# umodular_midi4_rev02.net
KiCad netlist of a schematic drawn in EAGLE
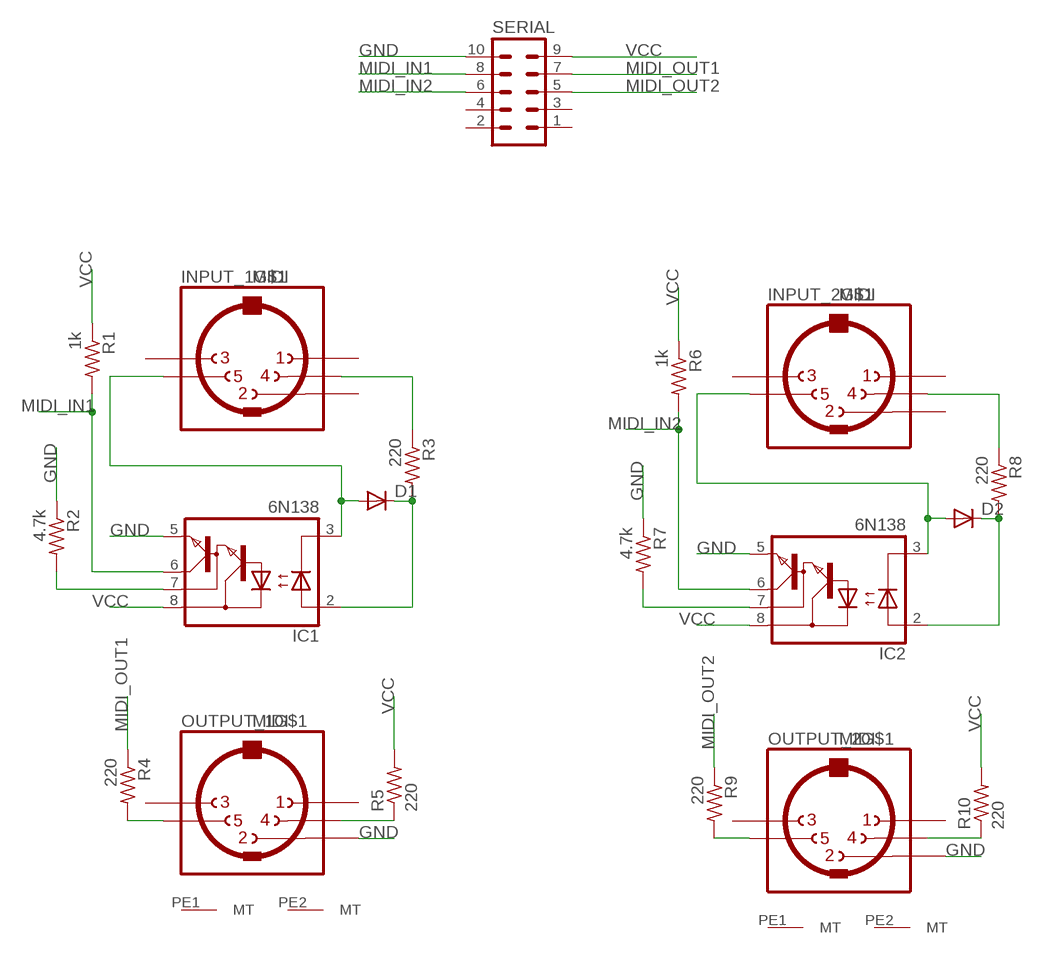
[diagram p0: schematic, sheet 1]

(export (version "E")
  (design (tool "Eeschema 10.0.6"))
  (components
    (comp (ref "D1")
      (value "1N4148DO35-7")
      (footprint "eagle-import:DO35-7")
      (libsource (lib "eagle-import") (part "1N4148DO35-7"))
    )
    (comp (ref "D2")
      (value "1N4148DO35-7")
      (footprint "eagle-import:DO35-7")
      (libsource (lib "eagle-import") (part "1N4148DO35-7"))
    )
    (comp (ref "IC1")
      (value "6N138")
      (footprint "eagle-import:DIL08")
      (fields (field (name "MF") "VISHAY/TELEFUNKEN"))
      (libsource (lib "eagle-import") (part "6N138"))
    )
    (comp (ref "IC2")
      (value "6N138")
      (footprint "eagle-import:DIL08")
      (fields (field (name "MF") "VISHAY/TELEFUNKEN"))
      (libsource (lib "eagle-import") (part "6N138"))
    )
    (comp (ref "INPUT_1")
      (value "MIDI")
      (footprint "eagle-import:CP-2350")
      (libsource (lib "eagle-import") (part "MIDIJACK"))
    )
    (comp (ref "INPUT_2")
      (value "MIDI")
      (footprint "eagle-import:CP-2350")
      (libsource (lib "eagle-import") (part "MIDIJACK"))
    )
    (comp (ref "OUTPUT_1")
      (value "MIDI")
      (footprint "eagle-import:CP-2350")
      (libsource (lib "eagle-import") (part "MIDIJACK"))
    )
    (comp (ref "OUTPUT_2")
      (value "MIDI")
      (footprint "eagle-import:CP-2350")
      (libsource (lib "eagle-import") (part "MIDIJACK"))
    )
    (comp (ref "R1")
      (value "1k")
      (footprint "eagle-import:0204_7@1")
      (libsource (lib "eagle-import") (part "R-US_0204/7"))
    )
    (comp (ref "R2")
      (value "4.7k")
      (footprint "eagle-import:0204_7@1")
      (libsource (lib "eagle-import") (part "R-US_0204/7"))
    )
    (comp (ref "R3")
      (value "220")
      (footprint "eagle-import:0204_7@1")
      (libsource (lib "eagle-import") (part "R-US_0204/7"))
    )
    (comp (ref "R4")
      (value "220")
      (footprint "eagle-import:0204_7@1")
      (libsource (lib "eagle-import") (part "R-US_0204/7"))
    )
    (comp (ref "R5")
      (value "220")
      (footprint "eagle-import:0204_7@1")
      (libsource (lib "eagle-import") (part "R-US_0204/7"))
    )
    (comp (ref "R6")
      (value "1k")
      (footprint "eagle-import:0204_7@1")
      (libsource (lib "eagle-import") (part "R-US_0204/7"))
    )
    (comp (ref "R7")
      (value "4.7k")
      (footprint "eagle-import:0204_7@1")
      (libsource (lib "eagle-import") (part "R-US_0204/7"))
    )
    (comp (ref "R8")
      (value "220")
      (footprint "eagle-import:0204_7@1")
      (libsource (lib "eagle-import") (part "R-US_0204/7"))
    )
    (comp (ref "R9")
      (value "220")
      (footprint "eagle-import:0204_7@1")
      (libsource (lib "eagle-import") (part "R-US_0204/7"))
    )
    (comp (ref "R10")
      (value "220")
      (footprint "eagle-import:0204_7@1")
      (libsource (lib "eagle-import") (part "R-US_0204/7"))
    )
    (comp (ref "SERIAL")
      (value "MA05-2")
      (footprint "eagle-import:MA05-2")
      (libsource (lib "eagle-import") (part "MA05-2"))
    )
  )
  (nets
    (net (code "1") (name "/GND") (class "Default")
      (node (ref "IC1") (pin "5") (pinfunction "GND_5") (pintype "passive"))
      (node (ref "IC2") (pin "5") (pinfunction "GND_5") (pintype "passive"))
      (node (ref "OUTPUT_1") (pin "2") (pinfunction "2_2") (pintype "passive"))
      (node (ref "OUTPUT_2") (pin "2") (pinfunction "2_2") (pintype "passive"))
      (node (ref "R2") (pin "1") (pinfunction "1_1") (pintype "passive"))
      (node (ref "R7") (pin "1") (pinfunction "1_1") (pintype "passive"))
      (node (ref "SERIAL") (pin "10") (pinfunction "10_10") (pintype "passive"))
    )
    (net (code "2") (name "/MIDI_IN1") (class "Default")
      (node (ref "IC1") (pin "6") (pinfunction "VO_6") (pintype "passive"))
      (node (ref "R1") (pin "2") (pinfunction "2_2") (pintype "passive"))
      (node (ref "SERIAL") (pin "8") (pinfunction "8_8") (pintype "passive"))
    )
    (net (code "3") (name "/MIDI_IN2") (class "Default")
      (node (ref "IC2") (pin "6") (pinfunction "VO_6") (pintype "passive"))
      (node (ref "R6") (pin "2") (pinfunction "2_2") (pintype "passive"))
      (node (ref "SERIAL") (pin "6") (pinfunction "6_6") (pintype "passive"))
    )
    (net (code "4") (name "/MIDI_OUT1") (class "Default")
      (node (ref "R4") (pin "1") (pinfunction "1_1") (pintype "passive"))
      (node (ref "SERIAL") (pin "7") (pinfunction "7_7") (pintype "passive"))
    )
    (net (code "5") (name "/MIDI_OUT2") (class "Default")
      (node (ref "R9") (pin "1") (pinfunction "1_1") (pintype "passive"))
      (node (ref "SERIAL") (pin "5") (pinfunction "5_5") (pintype "passive"))
    )
    (net (code "6") (name "/VCC") (class "Default")
      (node (ref "IC1") (pin "8") (pinfunction "VCC_8") (pintype "passive"))
      (node (ref "IC2") (pin "8") (pinfunction "VCC_8") (pintype "passive"))
      (node (ref "R1") (pin "1") (pinfunction "1_1") (pintype "passive"))
      (node (ref "R10") (pin "2") (pinfunction "2_2") (pintype "passive"))
      (node (ref "R5") (pin "2") (pinfunction "2_2") (pintype "passive"))
      (node (ref "R6") (pin "1") (pinfunction "1_1") (pintype "passive"))
      (node (ref "SERIAL") (pin "9") (pinfunction "9_9") (pintype "passive"))
    )
    (net (code "7") (name "Net-(IC1-A)") (class "Default")
      (node (ref "D1") (pin "C") (pinfunction "C_C") (pintype "passive"))
      (node (ref "IC1") (pin "2") (pinfunction "A_2") (pintype "passive"))
      (node (ref "R3") (pin "2") (pinfunction "2_2") (pintype "passive"))
    )
    (net (code "8") (name "Net-(IC1-C)") (class "Default")
      (node (ref "D1") (pin "A") (pinfunction "A_A") (pintype "passive"))
      (node (ref "IC1") (pin "3") (pinfunction "C_3") (pintype "passive"))
      (node (ref "INPUT_1") (pin "5") (pinfunction "5_5") (pintype "passive"))
    )
    (net (code "9") (name "Net-(IC1-VB)") (class "Default")
      (node (ref "IC1") (pin "7") (pinfunction "VB_7") (pintype "passive"))
      (node (ref "R2") (pin "2") (pinfunction "2_2") (pintype "passive"))
    )
    (net (code "10") (name "Net-(IC2-A)") (class "Default")
      (node (ref "D2") (pin "C") (pinfunction "C_C") (pintype "passive"))
      (node (ref "IC2") (pin "2") (pinfunction "A_2") (pintype "passive"))
      (node (ref "R8") (pin "2") (pinfunction "2_2") (pintype "passive"))
    )
    (net (code "11") (name "Net-(IC2-C)") (class "Default")
      (node (ref "D2") (pin "A") (pinfunction "A_A") (pintype "passive"))
      (node (ref "IC2") (pin "3") (pinfunction "C_3") (pintype "passive"))
      (node (ref "INPUT_2") (pin "5") (pinfunction "5_5") (pintype "passive"))
    )
    (net (code "12") (name "Net-(IC2-VB)") (class "Default")
      (node (ref "IC2") (pin "7") (pinfunction "VB_7") (pintype "passive"))
      (node (ref "R7") (pin "2") (pinfunction "2_2") (pintype "passive"))
    )
    (net (code "13") (name "Net-(INPUT_1-Pad4)") (class "Default")
      (node (ref "INPUT_1") (pin "4") (pinfunction "4_4") (pintype "passive"))
      (node (ref "R3") (pin "1") (pinfunction "1_1") (pintype "passive"))
    )
    (net (code "14") (name "Net-(INPUT_2-Pad4)") (class "Default")
      (node (ref "INPUT_2") (pin "4") (pinfunction "4_4") (pintype "passive"))
      (node (ref "R8") (pin "1") (pinfunction "1_1") (pintype "passive"))
    )
    (net (code "15") (name "Net-(OUTPUT_1-Pad4)") (class "Default")
      (node (ref "OUTPUT_1") (pin "4") (pinfunction "4_4") (pintype "passive"))
      (node (ref "R5") (pin "1") (pinfunction "1_1") (pintype "passive"))
    )
    (net (code "16") (name "Net-(OUTPUT_1-Pad5)") (class "Default")
      (node (ref "OUTPUT_1") (pin "5") (pinfunction "5_5") (pintype "passive"))
      (node (ref "R4") (pin "2") (pinfunction "2_2") (pintype "passive"))
    )
    (net (code "17") (name "Net-(OUTPUT_2-Pad4)") (class "Default")
      (node (ref "OUTPUT_2") (pin "4") (pinfunction "4_4") (pintype "passive"))
      (node (ref "R10") (pin "1") (pinfunction "1_1") (pintype "passive"))
    )
    (net (code "18") (name "Net-(OUTPUT_2-Pad5)") (class "Default")
      (node (ref "OUTPUT_2") (pin "5") (pinfunction "5_5") (pintype "passive"))
      (node (ref "R9") (pin "2") (pinfunction "2_2") (pintype "passive"))
    )
    (net (code "19") (name "unconnected-(INPUT_1-Pad1)") (class "Default")
      (node (ref "INPUT_1") (pin "1") (pinfunction "1_1") (pintype "passive"))
    )
    (net (code "20") (name "unconnected-(INPUT_1-Pad2)") (class "Default")
      (node (ref "INPUT_1") (pin "2") (pinfunction "2_2") (pintype "passive"))
    )
    (net (code "21") (name "unconnected-(INPUT_1-Pad3)") (class "Default")
      (node (ref "INPUT_1") (pin "3") (pinfunction "3_3") (pintype "passive"))
    )
    (net (code "22") (name "unconnected-(INPUT_2-Pad1)") (class "Default")
      (node (ref "INPUT_2") (pin "1") (pinfunction "1_1") (pintype "passive"))
    )
    (net (code "23") (name "unconnected-(INPUT_2-Pad2)") (class "Default")
      (node (ref "INPUT_2") (pin "2") (pinfunction "2_2") (pintype "passive"))
    )
    (net (code "24") (name "unconnected-(INPUT_2-Pad3)") (class "Default")
      (node (ref "INPUT_2") (pin "3") (pinfunction "3_3") (pintype "passive"))
    )
    (net (code "25") (name "unconnected-(OUTPUT_1-Pad1)") (class "Default")
      (node (ref "OUTPUT_1") (pin "1") (pinfunction "1_1") (pintype "passive"))
    )
    (net (code "26") (name "unconnected-(OUTPUT_1-Pad3)") (class "Default")
      (node (ref "OUTPUT_1") (pin "3") (pinfunction "3_3") (pintype "passive"))
    )
    (net (code "27") (name "unconnected-(OUTPUT_1D-MT-PadPE1)") (class "Default")
      (node (ref "OUTPUT_1") (pin "PE1") (pinfunction "MT_PE1") (pintype "passive"))
    )
    (net (code "28") (name "unconnected-(OUTPUT_1E-MT-PadPE2)") (class "Default")
      (node (ref "OUTPUT_1") (pin "PE2") (pinfunction "MT_PE2") (pintype "passive"))
    )
    (net (code "29") (name "unconnected-(OUTPUT_2-Pad1)") (class "Default")
      (node (ref "OUTPUT_2") (pin "1") (pinfunction "1_1") (pintype "passive"))
    )
    (net (code "30") (name "unconnected-(OUTPUT_2-Pad3)") (class "Default")
      (node (ref "OUTPUT_2") (pin "3") (pinfunction "3_3") (pintype "passive"))
    )
    (net (code "31") (name "unconnected-(OUTPUT_2D-MT-PadPE1)") (class "Default")
      (node (ref "OUTPUT_2") (pin "PE1") (pinfunction "MT_PE1") (pintype "passive"))
    )
    (net (code "32") (name "unconnected-(OUTPUT_2E-MT-PadPE2)") (class "Default")
      (node (ref "OUTPUT_2") (pin "PE2") (pinfunction "MT_PE2") (pintype "passive"))
    )
    (net (code "33") (name "unconnected-(SERIAL-Pad1)") (class "Default")
      (node (ref "SERIAL") (pin "1") (pinfunction "1_1") (pintype "passive"))
    )
    (net (code "34") (name "unconnected-(SERIAL-Pad2)") (class "Default")
      (node (ref "SERIAL") (pin "2") (pinfunction "2_2") (pintype "passive"))
    )
    (net (code "35") (name "unconnected-(SERIAL-Pad3)") (class "Default")
      (node (ref "SERIAL") (pin "3") (pinfunction "3_3") (pintype "passive"))
    )
    (net (code "36") (name "unconnected-(SERIAL-Pad4)") (class "Default")
      (node (ref "SERIAL") (pin "4") (pinfunction "4_4") (pintype "passive"))
    )
  )
)
